# relay.net
KiCad netlist of a schematic drawn in Altium Designer
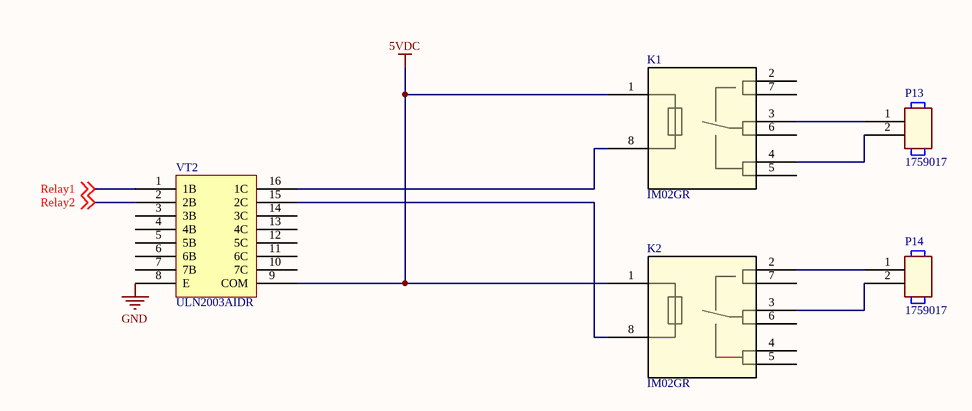
[diagram p0: relay.SchDoc]

(export (version "E")
  (design (tool "Eeschema 10.0.6"))
  (components
    (comp (ref "K1")
      (value "IM02GR")
      (footprint "IM-Gull")
      (description "Signal Relay; Coil Voltage VDC Nom:4.5V")
      (libsource (lib "spider") (part "IM02GR"))
    )
    (comp (ref "K2")
      (value "IM02GR")
      (footprint "IM-Gull")
      (description "Signal Relay; Coil Voltage VDC Nom:4.5V")
      (libsource (lib "spider") (part "IM02GR"))
    )
    (comp (ref "P13")
      (value "TE_282814-2")
      (footprint "TE_282814-2")
      (description "Terminal Block Connectors")
      (fields (field (name "MANUFACTURER") "TE Connectivity") (field (name "P/N2") "1759017"))
      (libsource (lib "spider") (part "TE_282814-2"))
    )
    (comp (ref "P14")
      (value "TE_282814-2")
      (footprint "TE_282814-2")
      (description "Terminal Block Connectors")
      (fields (field (name "MANUFACTURER") "TE Connectivity") (field (name "P/N2") "1759017"))
      (libsource (lib "spider") (part "TE_282814-2"))
    )
    (comp (ref "VT2")
      (value "ULN2003A")
      (footprint "SO-G16")
      (description "DARLINGTON TRANSISTOR ARRAYS")
      (fields (field (name "MANUFACTURER") "TI") (field (name "P/N") "ULN2003AIDR"))
      (libsource (lib "spider") (part "ULN2003A"))
    )
  )
  (nets
    (net (code "1") (name "5VDC") (class "Default")
      (node (ref "K1") (pin "1") (pinfunction "C+_1") (pintype "passive"))
      (node (ref "K2") (pin "1") (pinfunction "C+_1") (pintype "passive"))
      (node (ref "VT2") (pin "9") (pinfunction "COM_9") (pintype "passive"))
    )
    (net (code "2") (name "GND") (class "Default")
      (node (ref "VT2") (pin "8") (pinfunction "E_8") (pintype "passive"))
    )
    (net (code "3") (name "Net-(K1-A1)") (class "Default")
      (node (ref "K1") (pin "4") (pinfunction "A1_4") (pintype "passive"))
      (node (ref "P13") (pin "2") (pinfunction "2_2") (pintype "passive"))
    )
    (net (code "4") (name "Net-(K1-C-)") (class "Default")
      (node (ref "K1") (pin "8") (pinfunction "C-_8") (pintype "passive"))
      (node (ref "VT2") (pin "16") (pinfunction "1C_16") (pintype "passive"))
    )
    (net (code "5") (name "Net-(K1-S1)") (class "Default")
      (node (ref "K1") (pin "3") (pinfunction "S1_3") (pintype "passive"))
      (node (ref "P13") (pin "1") (pinfunction "1_1") (pintype "passive"))
    )
    (net (code "6") (name "Net-(K2-C-)") (class "Default")
      (node (ref "K2") (pin "8") (pinfunction "C-_8") (pintype "passive"))
      (node (ref "VT2") (pin "15") (pinfunction "2C_15") (pintype "passive"))
    )
    (net (code "7") (name "Net-(K2-I1)") (class "Default")
      (node (ref "K2") (pin "2") (pinfunction "I1_2") (pintype "passive"))
      (node (ref "P14") (pin "1") (pinfunction "1_1") (pintype "passive"))
    )
    (net (code "8") (name "Net-(K2-S1)") (class "Default")
      (node (ref "K2") (pin "3") (pinfunction "S1_3") (pintype "passive"))
      (node (ref "P14") (pin "2") (pinfunction "2_2") (pintype "passive"))
    )
    (net (code "9") (name "Relay1") (class "Default")
      (node (ref "VT2") (pin "1") (pinfunction "1B_1") (pintype "passive"))
    )
    (net (code "10") (name "Relay2") (class "Default")
      (node (ref "VT2") (pin "2") (pinfunction "2B_2") (pintype "passive"))
    )
    (net (code "11") (name "unconnected-(K1-A2-Pad5)") (class "Default")
      (node (ref "K1") (pin "5") (pinfunction "A2_5") (pintype "passive"))
    )
    (net (code "12") (name "unconnected-(K1-I1-Pad2)") (class "Default")
      (node (ref "K1") (pin "2") (pinfunction "I1_2") (pintype "passive"))
    )
    (net (code "13") (name "unconnected-(K1-I2-Pad7)") (class "Default")
      (node (ref "K1") (pin "7") (pinfunction "I2_7") (pintype "passive"))
    )
    (net (code "14") (name "unconnected-(K1-S2-Pad6)") (class "Default")
      (node (ref "K1") (pin "6") (pinfunction "S2_6") (pintype "passive"))
    )
    (net (code "15") (name "unconnected-(K2-A1-Pad4)") (class "Default")
      (node (ref "K2") (pin "4") (pinfunction "A1_4") (pintype "passive"))
    )
    (net (code "16") (name "unconnected-(K2-A2-Pad5)") (class "Default")
      (node (ref "K2") (pin "5") (pinfunction "A2_5") (pintype "passive"))
    )
    (net (code "17") (name "unconnected-(K2-I2-Pad7)") (class "Default")
      (node (ref "K2") (pin "7") (pinfunction "I2_7") (pintype "passive"))
    )
    (net (code "18") (name "unconnected-(K2-S2-Pad6)") (class "Default")
      (node (ref "K2") (pin "6") (pinfunction "S2_6") (pintype "passive"))
    )
    (net (code "19") (name "unconnected-(VT2-3B-Pad3)") (class "Default")
      (node (ref "VT2") (pin "3") (pinfunction "3B_3") (pintype "passive"))
    )
    (net (code "20") (name "unconnected-(VT2-3C-Pad14)") (class "Default")
      (node (ref "VT2") (pin "14") (pinfunction "3C_14") (pintype "passive"))
    )
    (net (code "21") (name "unconnected-(VT2-4B-Pad4)") (class "Default")
      (node (ref "VT2") (pin "4") (pinfunction "4B_4") (pintype "passive"))
    )
    (net (code "22") (name "unconnected-(VT2-4C-Pad13)") (class "Default")
      (node (ref "VT2") (pin "13") (pinfunction "4C_13") (pintype "passive"))
    )
    (net (code "23") (name "unconnected-(VT2-5B-Pad5)") (class "Default")
      (node (ref "VT2") (pin "5") (pinfunction "5B_5") (pintype "passive"))
    )
    (net (code "24") (name "unconnected-(VT2-5C-Pad12)") (class "Default")
      (node (ref "VT2") (pin "12") (pinfunction "5C_12") (pintype "passive"))
    )
    (net (code "25") (name "unconnected-(VT2-6B-Pad6)") (class "Default")
      (node (ref "VT2") (pin "6") (pinfunction "6B_6") (pintype "passive"))
    )
    (net (code "26") (name "unconnected-(VT2-6C-Pad11)") (class "Default")
      (node (ref "VT2") (pin "11") (pinfunction "6C_11") (pintype "passive"))
    )
    (net (code "27") (name "unconnected-(VT2-7B-Pad7)") (class "Default")
      (node (ref "VT2") (pin "7") (pinfunction "7B_7") (pintype "passive"))
    )
    (net (code "28") (name "unconnected-(VT2-7C-Pad10)") (class "Default")
      (node (ref "VT2") (pin "10") (pinfunction "7C_10") (pintype "passive"))
    )
  )
)
